# Master_V4_1.net
KiCad netlist of a schematic drawn in Altium Designer
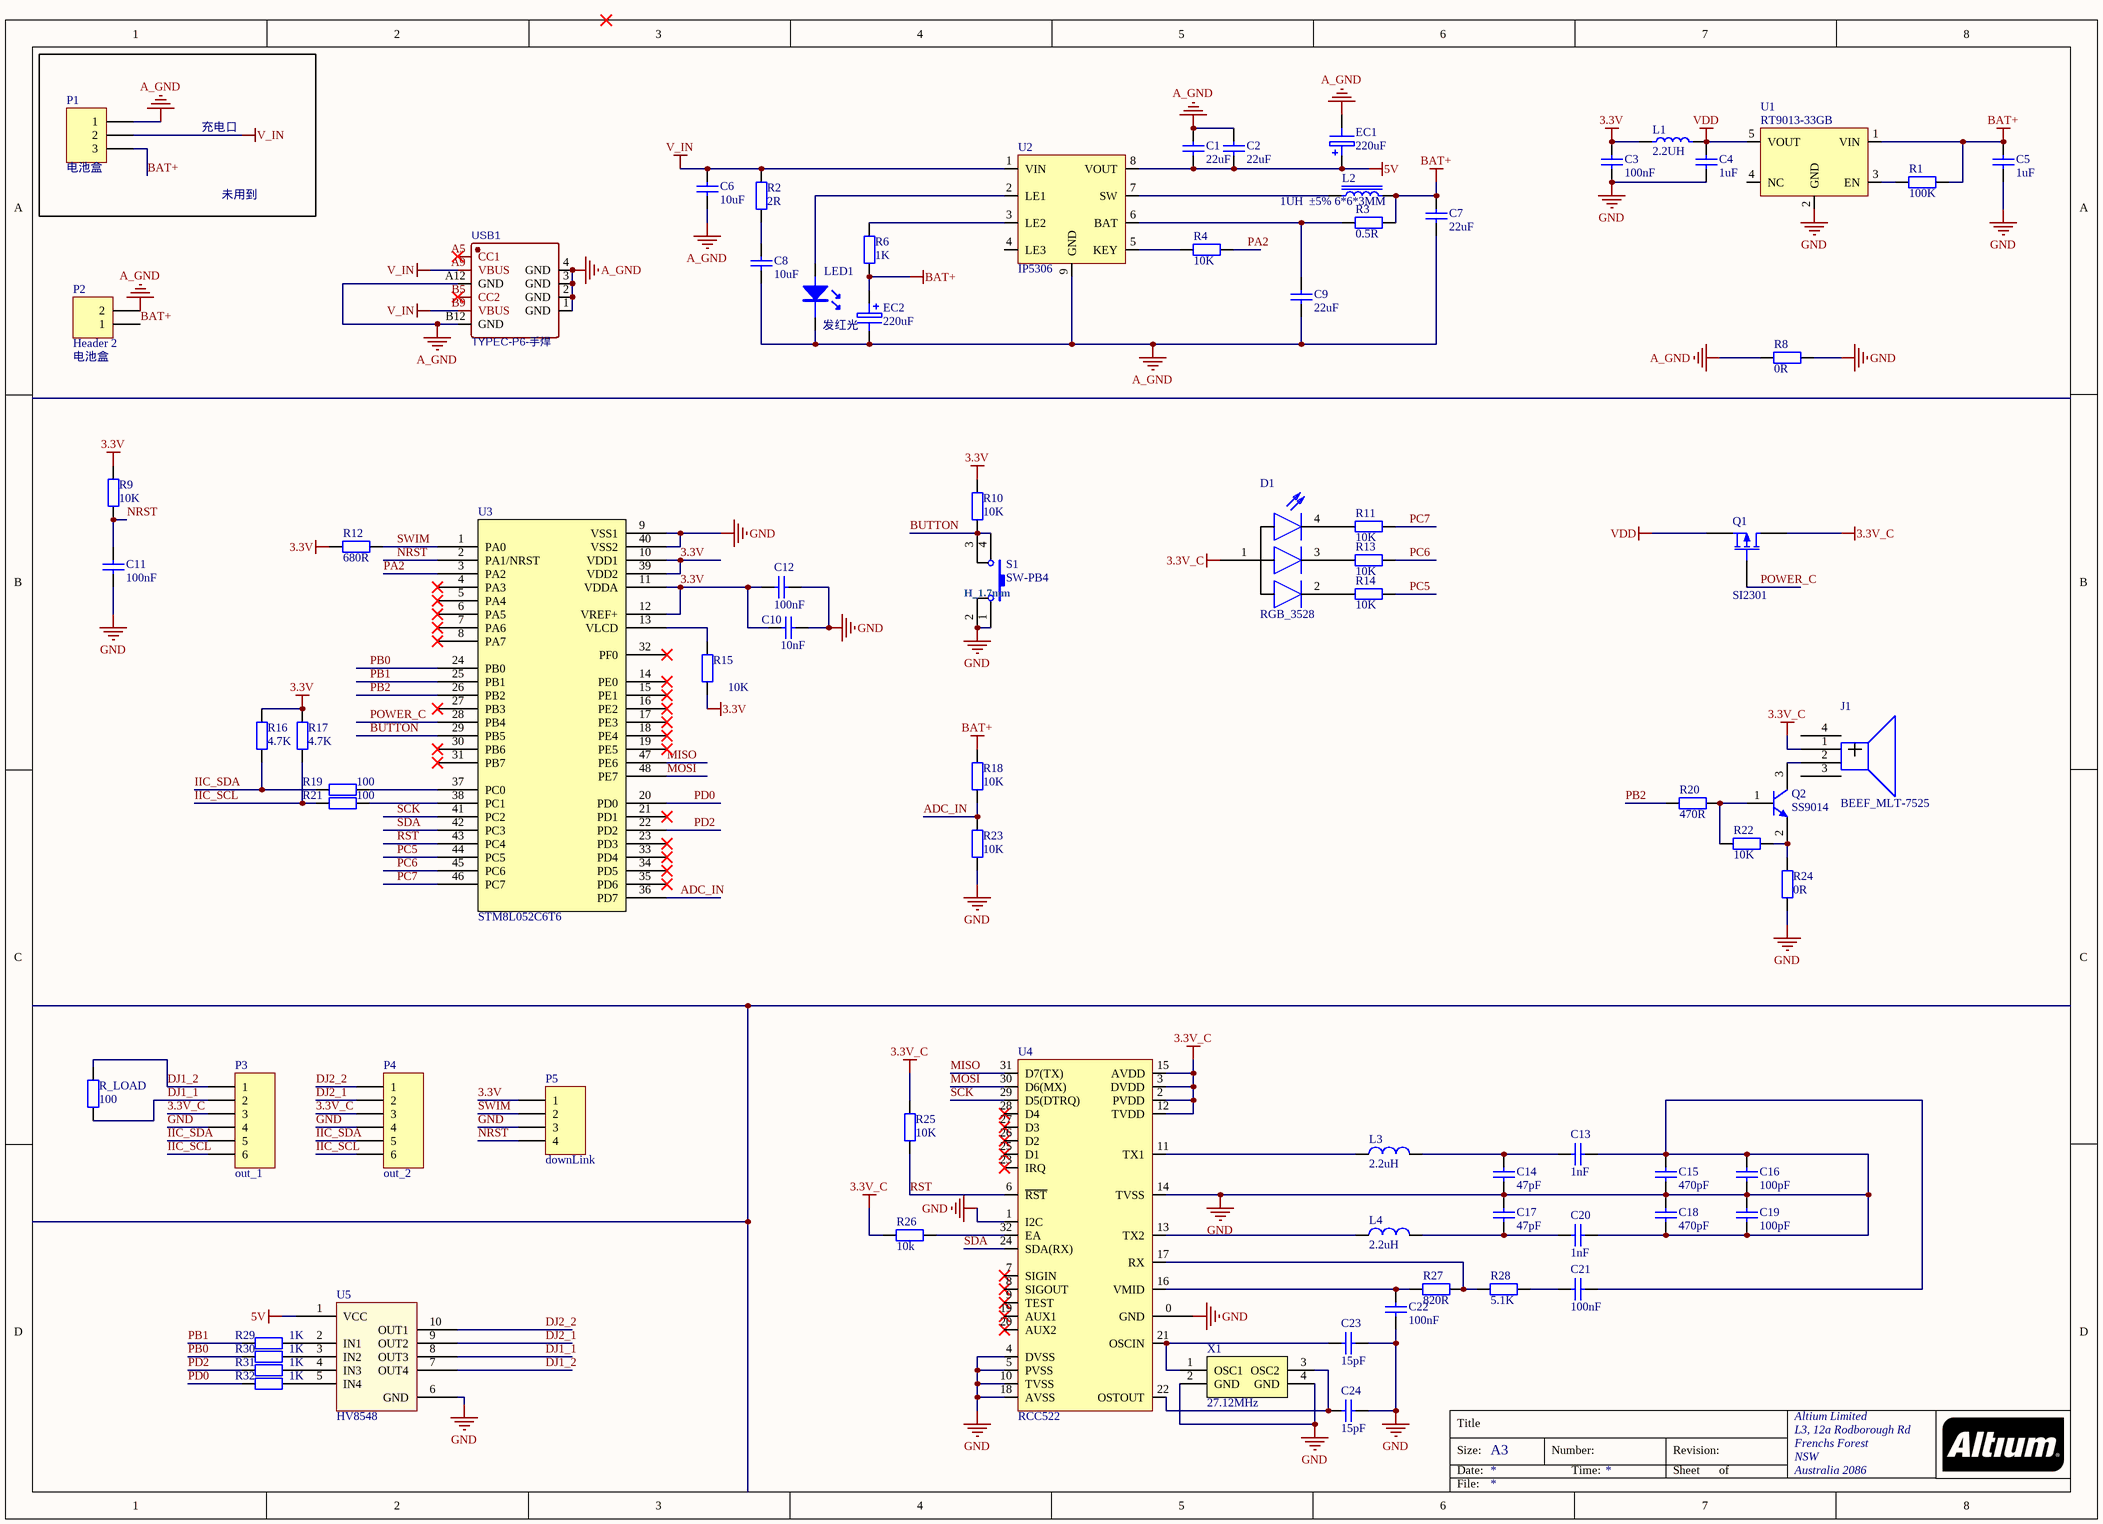
[diagram p0: Master_V4.1.SchDoc]

(export (version "E")
  (design (tool "Eeschema 10.0.6"))
  (components
    (comp (ref "C1")
      (value "22uF")
      (footprint "C-0603")
      (description "贴片瓷片电容")
      (fields (field (name "PUBLISHER") "Altium Limited"))
      (libsource (lib "PCB_Project") (part "22uF"))
    )
    (comp (ref "C2")
      (value "22uF")
      (footprint "C-0603")
      (description "贴片瓷片电容")
      (fields (field (name "PUBLISHER") "Altium Limited"))
      (libsource (lib "PCB_Project") (part "22uF"))
    )
    (comp (ref "C3")
      (value "100nF")
      (footprint "C-0603")
      (description "贴片瓷片电容")
      (fields (field (name "PUBLISHER") "Altium Limited"))
      (libsource (lib "PCB_Project") (part "100nF"))
    )
    (comp (ref "C4")
      (value "1uF")
      (footprint "C-0603")
      (description "贴片瓷片电容")
      (fields (field (name "PUBLISHER") "Altium Limited"))
      (libsource (lib "PCB_Project") (part "1uF"))
    )
    (comp (ref "C5")
      (value "1uF")
      (footprint "C-0603")
      (description "贴片瓷片电容")
      (fields (field (name "PUBLISHER") "Altium Limited"))
      (libsource (lib "PCB_Project") (part "1uF"))
    )
    (comp (ref "C6")
      (value "10uF")
      (footprint "C-0603")
      (description "贴片瓷片电容")
      (fields (field (name "PUBLISHER") "Altium Limited"))
      (libsource (lib "PCB_Project") (part "10uF"))
    )
    (comp (ref "C7")
      (value "22uF")
      (footprint "C-0603")
      (description "贴片瓷片电容")
      (fields (field (name "PUBLISHER") "Altium Limited"))
      (libsource (lib "PCB_Project") (part "22uF"))
    )
    (comp (ref "C8")
      (value "10uF")
      (footprint "C-0603")
      (description "贴片瓷片电容")
      (fields (field (name "PUBLISHER") "Altium Limited"))
      (libsource (lib "PCB_Project") (part "10uF"))
    )
    (comp (ref "C9")
      (value "22uF")
      (footprint "C-0603")
      (description "贴片瓷片电容")
      (fields (field (name "PUBLISHER") "Altium Limited"))
      (libsource (lib "PCB_Project") (part "22uF"))
    )
    (comp (ref "C10")
      (value "10nF")
      (footprint "C-0603")
      (description "贴片瓷片电容")
      (fields (field (name "PUBLISHER") "Altium Limited"))
      (libsource (lib "PCB_Project") (part "10nF"))
    )
    (comp (ref "C11")
      (value "100nF")
      (footprint "C-0603")
      (description "贴片瓷片电容")
      (fields (field (name "PUBLISHER") "Altium Limited"))
      (libsource (lib "PCB_Project") (part "100nF"))
    )
    (comp (ref "C12")
      (value "100nF")
      (footprint "C-0603")
      (description "贴片瓷片电容")
      (fields (field (name "PUBLISHER") "Altium Limited"))
      (libsource (lib "PCB_Project") (part "100nF"))
    )
    (comp (ref "C13")
      (value "1nF")
      (footprint "C-0603")
      (description "贴片瓷片电容")
      (fields (field (name "PUBLISHER") "Altium Limited"))
      (libsource (lib "PCB_Project") (part "1nF"))
    )
    (comp (ref "C14")
      (value "47pF")
      (footprint "C-0603")
      (description "贴片瓷片电容")
      (fields (field (name "PUBLISHER") "Altium Limited"))
      (libsource (lib "PCB_Project") (part "47pF"))
    )
    (comp (ref "C15")
      (value "470pF")
      (footprint "C-0603")
      (description "贴片瓷片电容")
      (fields (field (name "PUBLISHER") "Altium Limited"))
      (libsource (lib "PCB_Project") (part "470pF"))
    )
    (comp (ref "C16")
      (value "100pF")
      (footprint "C-0603")
      (description "贴片瓷片电容")
      (fields (field (name "PUBLISHER") "Altium Limited"))
      (libsource (lib "PCB_Project") (part "100pF"))
    )
    (comp (ref "C17")
      (value "47pF")
      (footprint "C-0603")
      (description "贴片瓷片电容")
      (fields (field (name "PUBLISHER") "Altium Limited"))
      (libsource (lib "PCB_Project") (part "47pF"))
    )
    (comp (ref "C18")
      (value "470pF")
      (footprint "C-0603")
      (description "贴片瓷片电容")
      (fields (field (name "PUBLISHER") "Altium Limited"))
      (libsource (lib "PCB_Project") (part "470pF"))
    )
    (comp (ref "C19")
      (value "100pF")
      (footprint "C-0603")
      (description "贴片瓷片电容")
      (fields (field (name "PUBLISHER") "Altium Limited"))
      (libsource (lib "PCB_Project") (part "100pF"))
    )
    (comp (ref "C20")
      (value "1nF")
      (footprint "C-0603")
      (description "贴片瓷片电容")
      (fields (field (name "PUBLISHER") "Altium Limited"))
      (libsource (lib "PCB_Project") (part "1nF"))
    )
    (comp (ref "C21")
      (value "100nF")
      (footprint "C-0603")
      (description "贴片瓷片电容")
      (fields (field (name "PUBLISHER") "Altium Limited"))
      (libsource (lib "PCB_Project") (part "100nF"))
    )
    (comp (ref "C22")
      (value "100nF")
      (footprint "C-0603")
      (description "贴片瓷片电容")
      (fields (field (name "PUBLISHER") "Altium Limited"))
      (libsource (lib "PCB_Project") (part "100nF"))
    )
    (comp (ref "C23")
      (value "15pF")
      (footprint "C-0603")
      (description "贴片瓷片电容")
      (fields (field (name "PUBLISHER") "Altium Limited"))
      (libsource (lib "PCB_Project") (part "15pF"))
    )
    (comp (ref "C24")
      (value "15pF")
      (footprint "C-0603")
      (description "贴片瓷片电容")
      (fields (field (name "PUBLISHER") "Altium Limited"))
      (libsource (lib "PCB_Project") (part "15pF"))
    )
    (comp (ref "D1")
      (value "RGB_3528")
      (footprint "SMD3528")
      (libsource (lib "PCB_Project") (part "RGB_3528"))
    )
    (comp (ref "EC1")
      (value "220uF")
      (footprint "CAP-3528")
      (description "3528钽电容")
      (libsource (lib "PCB_Project") (part "220uF"))
    )
    (comp (ref "EC2")
      (value "220uF")
      (footprint "CAP-3528")
      (description "3528钽电容")
      (libsource (lib "PCB_Project") (part "220uF"))
    )
    (comp (ref "J1")
      (value "BEEF_MLT-7525")
      (footprint "MLT-7525")
      (libsource (lib "SwipeMaster") (part "BEEF_MLT-7525"))
    )
    (comp (ref "L1") (value "2.2UH") (footprint "0805") (libsource (lib "*") (part "INCT")))
    (comp (ref "L2") (value "1UH  ±5% 6*6*3MM") (footprint "L") (libsource (lib "*") (part "INCT_1")))
    (comp (ref "L3") (value "2.2uH") (footprint "0805") (libsource (lib "Schlib1") (part "INDUCTANCE")))
    (comp (ref "L4") (value "2.2uH") (footprint "0805") (libsource (lib "Schlib1") (part "INDUCTANCE")))
    (comp (ref "LED1") (value "发红光") (footprint "LED0603_RED") (libsource (lib "*") (part "LED")))
    (comp (ref "P1")
      (value "电池盒")
      (footprint "POWER_3_改")
      (description "Header, 3-Pin")
      (fields (field (name "PUBLISHER") "Altium Limited"))
      (libsource (lib "Miscellaneous Connectors") (part "Header 3"))
    )
    (comp (ref "P2")
      (value "Header 2")
      (footprint "HDR1X2")
      (description "Header, 2-Pin")
      (fields (field (name "PUBLISHER") "Altium Limited"))
      (libsource (lib "Miscellaneous Connectors") (part "Header 2"))
    )
    (comp (ref "P3")
      (value "out_1")
      (footprint "乐高水晶头")
      (description "Header, 6-Pin")
      (fields (field (name "PUBLISHER") "Altium Limited"))
      (libsource (lib "Miscellaneous Connectors") (part "Header 6"))
    )
    (comp (ref "P4")
      (value "out_2")
      (footprint "乐高水晶头")
      (description "Header, 6-Pin")
      (fields (field (name "PUBLISHER") "Altium Limited"))
      (libsource (lib "Miscellaneous Connectors") (part "Header 6"))
    )
    (comp (ref "P5")
      (value "downLink")
      (footprint "DOWNLOAD_dan")
      (description "Header, 4-Pin")
      (fields (field (name "PUBLISHER") "Altium Limited"))
      (libsource (lib "Miscellaneous Connectors") (part "Header 4"))
    )
    (comp (ref "Q1")
      (value "SI2301")
      (footprint "SOT-23(SOT-23-3)")
      (description "P-Channel MOSFET")
      (fields (field (name "PUBLISHER") "Altium Limited"))
      (libsource (lib "Miscellaneous Devices") (part "MOSFET-P"))
    )
    (comp (ref "Q2")
      (value "SS9014")
      (footprint "SOT23-3")
      (description "NPN贴片三极管")
      (fields (field (name "PUBLISHER") "Altium Limited"))
      (libsource (lib "fszhang_P") (part "SS9014"))
    )
    (comp (ref "R1")
      (value "100K")
      (footprint "0603-1")
      (description "贴片电阻")
      (fields (field (name "PUBLISHER") "Altium Limited"))
      (libsource (lib "PCB_Project") (part "100K"))
    )
    (comp (ref "R2")
      (value "2R")
      (footprint "0603-1")
      (description "贴片电阻")
      (fields (field (name "PUBLISHER") "Altium Limited"))
      (libsource (lib "PCB_Project") (part "2R"))
    )
    (comp (ref "R3")
      (value "0.5R")
      (footprint "0603-1")
      (description "贴片电阻")
      (fields (field (name "PUBLISHER") "Altium Limited"))
      (libsource (lib "PCB_Project") (part "0.5R"))
    )
    (comp (ref "R4")
      (value "10K")
      (footprint "0603-1")
      (description "贴片电阻")
      (fields (field (name "PUBLISHER") "Altium Limited"))
      (libsource (lib "") (part "10K_1"))
    )
    (comp (ref "R6")
      (value "1K")
      (footprint "0603-1")
      (description "贴片电阻")
      (fields (field (name "PUBLISHER") "Altium Limited"))
      (libsource (lib "PCB_Project") (part "1K"))
    )
    (comp (ref "R8")
      (value "0R")
      (footprint "0603-1")
      (description "贴片电阻")
      (fields (field (name "PUBLISHER") "Altium Limited"))
      (libsource (lib "") (part "0R_1"))
    )
    (comp (ref "R9")
      (value "10K")
      (footprint "0603-1")
      (description "贴片电阻")
      (fields (field (name "PUBLISHER") "Altium Limited"))
      (libsource (lib "PCB_Project") (part "10K"))
    )
    (comp (ref "R10")
      (value "10K")
      (footprint "0603-1")
      (description "贴片电阻")
      (fields (field (name "PUBLISHER") "Altium Limited"))
      (libsource (lib "") (part "10K_1"))
    )
    (comp (ref "R11")
      (value "10K")
      (footprint "0603-1")
      (description "贴片电阻")
      (fields (field (name "PUBLISHER") "Altium Limited"))
      (libsource (lib "PCB_Project") (part "10K"))
    )
    (comp (ref "R12")
      (value "680R")
      (footprint "0603-1")
      (description "贴片电阻")
      (fields (field (name "PUBLISHER") "Altium Limited"))
      (libsource (lib "PCB_Project") (part "680R"))
    )
    (comp (ref "R13")
      (value "10K")
      (footprint "0603-1")
      (description "贴片电阻")
      (fields (field (name "PUBLISHER") "Altium Limited"))
      (libsource (lib "PCB_Project") (part "10K"))
    )
    (comp (ref "R14")
      (value "10K")
      (footprint "0603-1")
      (description "贴片电阻")
      (fields (field (name "PUBLISHER") "Altium Limited"))
      (libsource (lib "PCB_Project") (part "10K"))
    )
    (comp (ref "R15")
      (value "10K")
      (footprint "0603-1")
      (description "贴片电阻")
      (fields (field (name "PUBLISHER") "Altium Limited"))
      (libsource (lib "PCB_Project") (part "10K"))
    )
    (comp (ref "R16")
      (value "4.7K")
      (footprint "0603-1")
      (description "贴片电阻")
      (fields (field (name "PUBLISHER") "Altium Limited"))
      (libsource (lib "PCB_Project") (part "4.7K"))
    )
    (comp (ref "R17")
      (value "4.7K")
      (footprint "0603-1")
      (description "贴片电阻")
      (fields (field (name "PUBLISHER") "Altium Limited"))
      (libsource (lib "PCB_Project") (part "4.7K"))
    )
    (comp (ref "R18")
      (value "10K")
      (footprint "0603-1")
      (description "贴片电阻")
      (fields (field (name "PUBLISHER") "Altium Limited"))
      (libsource (lib "") (part "10K_2"))
    )
    (comp (ref "R19")
      (value "100")
      (footprint "0603-1")
      (description "贴片电阻")
      (fields (field (name "Comment") "Res1") (field (name "PUBLISHER") "Altium Limited"))
      (libsource (lib "fszhang_P") (part "Res1"))
    )
    (comp (ref "R20")
      (value "470R")
      (footprint "0603-1")
      (description "贴片电阻")
      (fields (field (name "PUBLISHER") "Altium Limited"))
      (libsource (lib "PCB_Project") (part "470R"))
    )
    (comp (ref "R21")
      (value "100")
      (footprint "0603-1")
      (description "贴片电阻")
      (fields (field (name "Comment") "Res1") (field (name "PUBLISHER") "Altium Limited"))
      (libsource (lib "fszhang_P") (part "Res1"))
    )
    (comp (ref "R22")
      (value "10K")
      (footprint "0603-1")
      (description "贴片电阻")
      (fields (field (name "PUBLISHER") "Altium Limited"))
      (libsource (lib "") (part "10K_1"))
    )
    (comp (ref "R23")
      (value "10K")
      (footprint "0603-1")
      (description "贴片电阻")
      (fields (field (name "PUBLISHER") "Altium Limited"))
      (libsource (lib "") (part "10K_2"))
    )
    (comp (ref "R24")
      (value "0R")
      (footprint "0603-1")
      (description "贴片电阻")
      (fields (field (name "PUBLISHER") "Altium Limited"))
      (libsource (lib "PCB_Project") (part "0R"))
    )
    (comp (ref "R25")
      (value "10K")
      (footprint "0603-1")
      (description "贴片电阻")
      (fields (field (name "PUBLISHER") "Altium Limited"))
      (libsource (lib "PCB_Project") (part "10K"))
    )
    (comp (ref "R26")
      (value "10k")
      (footprint "0603-1")
      (description "贴片电阻")
      (fields (field (name "PUBLISHER") "Altium Limited"))
      (libsource (lib "") (part "1K_1"))
    )
    (comp (ref "R27")
      (value "820R")
      (footprint "0603-1")
      (description "贴片电阻")
      (fields (field (name "PUBLISHER") "Altium Limited"))
      (libsource (lib "PCB_Project") (part "820R"))
    )
    (comp (ref "R28")
      (value "5.1K")
      (footprint "0603-1")
      (description "贴片电阻")
      (fields (field (name "PUBLISHER") "Altium Limited"))
      (libsource (lib "PCB_Project") (part "5.1K"))
    )
    (comp (ref "R29")
      (value "1K")
      (footprint "0603-1")
      (description "贴片电阻")
      (fields (field (name "PUBLISHER") "Altium Limited"))
      (libsource (lib "") (part "1K_1"))
    )
    (comp (ref "R30")
      (value "1K")
      (footprint "0603-1")
      (description "贴片电阻")
      (fields (field (name "PUBLISHER") "Altium Limited"))
      (libsource (lib "") (part "1K_1"))
    )
    (comp (ref "R31")
      (value "1K")
      (footprint "0603-1")
      (description "贴片电阻")
      (fields (field (name "PUBLISHER") "Altium Limited"))
      (libsource (lib "") (part "1K_1"))
    )
    (comp (ref "R32")
      (value "1K")
      (footprint "0603-1")
      (description "贴片电阻")
      (fields (field (name "PUBLISHER") "Altium Limited"))
      (libsource (lib "") (part "1K_1"))
    )
    (comp (ref "R_LOAD")
      (value "100")
      (footprint "0603-1")
      (description "贴片电阻")
      (fields (field (name "Comment") "Res1") (field (name "PUBLISHER") "Altium Limited"))
      (libsource (lib "") (part "Res1_1"))
    )
    (comp (ref "S1")
      (value "SW-PB4")
      (footprint "SMD_5*5mm")
      (description "微动开关")
      (fields (field (name "PUBLISHER") "Altium Limited"))
      (libsource (lib "fszhang_P") (part "SW-PB4"))
    )
    (comp (ref "U1") (value "RT9013-33GB") (footprint "SOT-23-5") (libsource (lib "*") (part "RT9013-33GB")))
    (comp (ref "U2") (value "IP5306") (footprint "SOP-8") (libsource (lib "*") (part "IP5306")))
    (comp (ref "U3")
      (value "STM8L052C6T6")
      (footprint "LQFP-48")
      (libsource (lib "SwipeMaster") (part "STM8L052C6T6"))
    )
    (comp (ref "U4")
      (value "RCC522")
      (footprint "QFN-32_5*5")
      (libsource (lib "SwipeMaster") (part "RCC522"))
    )
    (comp (ref "U5") (value "HV8548") (footprint "SOP10") (libsource (lib "XJL公司网口") (part "LV8548")))
    (comp (ref "USB1")
      (value "TYPEC-P6-手焊")
      (footprint "TYPE_C_6P")
      (fields
        (field (name "BOM_SUPPLIER PART") "C720626")
        (field (name "BOM_MANUFACTURER PART") "TYPEC-250D-BCP6")
        (field (name "CONTRIBUTOR") "LCSC")
      )
      (libsource (lib "Sheet_1_2021-06-05") (part "TYPEC-P6-手焊"))
    )
    (comp (ref "X1")
      (value "27.12MHz")
      (footprint "SMD_3225")
      (libsource (lib "SwipeMaster") (part "27.12MHz"))
    )
  )
  (nets
    (net (code "1") (name "/ADC_IN") (class "Default")
      (node (ref "R18") (pin "2") (pinfunction "2_2") (pintype "passive"))
      (node (ref "R23") (pin "1") (pinfunction "1_1") (pintype "passive"))
      (node (ref "U3") (pin "36") (pinfunction "PD7_36") (pintype "passive"))
    )
    (net (code "2") (name "/BUTTON") (class "Default")
      (node (ref "R10") (pin "1") (pinfunction "1_1") (pintype "passive"))
      (node (ref "S1") (pin "3") (pinfunction "3_3") (pintype "passive"))
      (node (ref "S1") (pin "4") (pinfunction "4_4") (pintype "passive"))
      (node (ref "U3") (pin "29") (pinfunction "PB5_29") (pintype "passive"))
    )
    (net (code "3") (name "/DJ1_1") (class "Default")
      (node (ref "P3") (pin "2") (pinfunction "2_2") (pintype "passive"))
      (node (ref "R_LOAD") (pin "2") (pinfunction "2_2") (pintype "passive"))
      (node (ref "U5") (pin "8") (pinfunction "OUT3_8") (pintype "passive"))
    )
    (net (code "4") (name "/DJ1_2") (class "Default")
      (node (ref "P3") (pin "1") (pinfunction "1_1") (pintype "passive"))
      (node (ref "R_LOAD") (pin "1") (pinfunction "1_1") (pintype "passive"))
      (node (ref "U5") (pin "7") (pinfunction "OUT4_7") (pintype "passive"))
    )
    (net (code "5") (name "/DJ2_1") (class "Default")
      (node (ref "P4") (pin "2") (pinfunction "2_2") (pintype "passive"))
      (node (ref "U5") (pin "9") (pinfunction "OUT2_9") (pintype "passive"))
    )
    (net (code "6") (name "/DJ2_2") (class "Default")
      (node (ref "P4") (pin "1") (pinfunction "1_1") (pintype "passive"))
      (node (ref "U5") (pin "10") (pinfunction "OUT1_10") (pintype "passive"))
    )
    (net (code "7") (name "/IIC_SCL") (class "Default")
      (node (ref "P3") (pin "6") (pinfunction "6_6") (pintype "passive"))
      (node (ref "P4") (pin "6") (pinfunction "6_6") (pintype "passive"))
      (node (ref "R17") (pin "1") (pinfunction "1_1") (pintype "passive"))
      (node (ref "R21") (pin "2") (pinfunction "2_2") (pintype "passive"))
    )
    (net (code "8") (name "/IIC_SDA") (class "Default")
      (node (ref "P3") (pin "5") (pinfunction "5_5") (pintype "passive"))
      (node (ref "P4") (pin "5") (pinfunction "5_5") (pintype "passive"))
      (node (ref "R16") (pin "1") (pinfunction "1_1") (pintype "passive"))
      (node (ref "R19") (pin "2") (pinfunction "2_2") (pintype "passive"))
    )
    (net (code "9") (name "/MISO") (class "Default")
      (node (ref "U3") (pin "47") (pinfunction "PE6_47") (pintype "passive"))
      (node (ref "U4") (pin "31") (pinfunction "D7(TX)_31") (pintype "passive"))
    )
    (net (code "10") (name "/MOSI") (class "Default")
      (node (ref "U3") (pin "48") (pinfunction "PE7_48") (pintype "passive"))
      (node (ref "U4") (pin "30") (pinfunction "D6(MX)_30") (pintype "passive"))
    )
    (net (code "11") (name "/NRST") (class "Default")
      (node (ref "C11") (pin "1") (pinfunction "1_1") (pintype "passive"))
      (node (ref "P5") (pin "4") (pinfunction "4_4") (pintype "passive"))
      (node (ref "R9") (pin "1") (pinfunction "1_1") (pintype "passive"))
      (node (ref "U3") (pin "2") (pinfunction "PA1/NRST_2") (pintype "passive"))
    )
    (net (code "12") (name "/PA2") (class "Default")
      (node (ref "R4") (pin "2") (pinfunction "2_2") (pintype "passive"))
      (node (ref "U3") (pin "3") (pinfunction "PA2_3") (pintype "passive"))
    )
    (net (code "13") (name "/PB0") (class "Default")
      (node (ref "R30") (pin "1") (pinfunction "1_1") (pintype "passive"))
      (node (ref "U3") (pin "24") (pinfunction "PB0_24") (pintype "passive"))
    )
    (net (code "14") (name "/PB1") (class "Default")
      (node (ref "R29") (pin "1") (pinfunction "1_1") (pintype "passive"))
      (node (ref "U3") (pin "25") (pinfunction "PB1_25") (pintype "passive"))
    )
    (net (code "15") (name "/PB2") (class "Default")
      (node (ref "R20") (pin "1") (pinfunction "1_1") (pintype "passive"))
      (node (ref "U3") (pin "26") (pinfunction "PB2_26") (pintype "passive"))
    )
    (net (code "16") (name "/PC5") (class "Default")
      (node (ref "R14") (pin "2") (pinfunction "2_2") (pintype "passive"))
      (node (ref "U3") (pin "44") (pinfunction "PC5_44") (pintype "passive"))
    )
    (net (code "17") (name "/PC6") (class "Default")
      (node (ref "R13") (pin "2") (pinfunction "2_2") (pintype "passive"))
      (node (ref "U3") (pin "45") (pinfunction "PC6_45") (pintype "passive"))
    )
    (net (code "18") (name "/PC7") (class "Default")
      (node (ref "R11") (pin "2") (pinfunction "2_2") (pintype "passive"))
      (node (ref "U3") (pin "46") (pinfunction "PC7_46") (pintype "passive"))
    )
    (net (code "19") (name "/PD0") (class "Default")
      (node (ref "R32") (pin "1") (pinfunction "1_1") (pintype "passive"))
      (node (ref "U3") (pin "20") (pinfunction "PD0_20") (pintype "passive"))
    )
    (net (code "20") (name "/PD2") (class "Default")
      (node (ref "R31") (pin "1") (pinfunction "1_1") (pintype "passive"))
      (node (ref "U3") (pin "22") (pinfunction "PD2_22") (pintype "passive"))
    )
    (net (code "21") (name "/POWER_C") (class "Default")
      (node (ref "Q1") (pin "1") (pinfunction "G_1") (pintype "passive"))
      (node (ref "U3") (pin "28") (pinfunction "PB4_28") (pintype "passive"))
    )
    (net (code "22") (name "/RST") (class "Default")
      (node (ref "R25") (pin "1") (pinfunction "1_1") (pintype "passive"))
      (node (ref "U3") (pin "43") (pinfunction "PC4_43") (pintype "passive"))
      (node (ref "U4") (pin "6") (pinfunction "~{RST}_6") (pintype "passive"))
    )
    (net (code "23") (name "/SCK") (class "Default")
      (node (ref "U3") (pin "41") (pinfunction "PC2_41") (pintype "passive"))
      (node (ref "U4") (pin "29") (pinfunction "D5(DTRQ)_29") (pintype "passive"))
    )
    (net (code "24") (name "/SDA") (class "Default")
      (node (ref "U3") (pin "42") (pinfunction "PC3_42") (pintype "passive"))
      (node (ref "U4") (pin "24") (pinfunction "SDA(RX)_24") (pintype "passive"))
    )
    (net (code "25") (name "/SWIM") (class "Default")
      (node (ref "P5") (pin "2") (pinfunction "2_2") (pintype "passive"))
      (node (ref "R12") (pin "2") (pinfunction "2_2") (pintype "passive"))
      (node (ref "U3") (pin "1") (pinfunction "PA0_1") (pintype "passive"))
    )
    (net (code "26") (name "3.3V") (class "Default")
      (node (ref "C10") (pin "2") (pinfunction "2_2") (pintype "passive"))
      (node (ref "C12") (pin "2") (pinfunction "2_2") (pintype "passive"))
      (node (ref "C3") (pin "1") (pinfunction "1_1") (pintype "passive"))
      (node (ref "L1") (pin "1") (pinfunction "1_1") (pintype "passive"))
      (node (ref "P5") (pin "1") (pinfunction "1_1") (pintype "passive"))
      (node (ref "R10") (pin "2") (pinfunction "2_2") (pintype "passive"))
      (node (ref "R12") (pin "1") (pinfunction "1_1") (pintype "passive"))
      (node (ref "R15") (pin "1") (pinfunction "1_1") (pintype "passive"))
      (node (ref "R16") (pin "2") (pinfunction "2_2") (pintype "passive"))
      (node (ref "R17") (pin "2") (pinfunction "2_2") (pintype "passive"))
      (node (ref "R9") (pin "2") (pinfunction "2_2") (pintype "passive"))
      (node (ref "U3") (pin "10") (pinfunction "VDD1_10") (pintype "passive"))
      (node (ref "U3") (pin "11") (pinfunction "VDDA_11") (pintype "passive"))
      (node (ref "U3") (pin "12") (pinfunction "VREF+_12") (pintype "passive"))
      (node (ref "U3") (pin "39") (pinfunction "VDD2_39") (pintype "passive"))
    )
    (net (code "27") (name "3.3V_C") (class "Default")
      (node (ref "D1") (pin "1") (pinfunction "1_1") (pintype "passive"))
      (node (ref "J1") (pin "1") (pinfunction "1_1") (pintype "passive"))
      (node (ref "P3") (pin "3") (pinfunction "3_3") (pintype "passive"))
      (node (ref "P4") (pin "3") (pinfunction "3_3") (pintype "passive"))
      (node (ref "Q1") (pin "3") (pinfunction "D_3") (pintype "passive"))
      (node (ref "R25") (pin "2") (pinfunction "2_2") (pintype "passive"))
      (node (ref "R26") (pin "1") (pinfunction "1_1") (pintype "passive"))
      (node (ref "U4") (pin "12") (pinfunction "TVDD_12") (pintype "passive"))
      (node (ref "U4") (pin "15") (pinfunction "AVDD_15") (pintype "passive"))
      (node (ref "U4") (pin "2") (pinfunction "PVDD_2") (pintype "passive"))
      (node (ref "U4") (pin "3") (pinfunction "DVDD_3") (pintype "passive"))
    )
    (net (code "28") (name "5V") (class "Default")
      (node (ref "C1") (pin "2") (pinfunction "2_2") (pintype "passive"))
      (node (ref "C2") (pin "2") (pinfunction "2_2") (pintype "passive"))
      (node (ref "EC1") (pin "1") (pinfunction "1_1") (pintype "passive"))
      (node (ref "U2") (pin "8") (pinfunction "VOUT_8") (pintype "passive"))
      (node (ref "U5") (pin "1") (pinfunction "VCC_1") (pintype "passive"))
    )
    (net (code "29") (name "A_GND") (class "Default")
      (node (ref "C1") (pin "1") (pinfunction "1_1") (pintype "passive"))
      (node (ref "C2") (pin "1") (pinfunction "1_1") (pintype "passive"))
      (node (ref "C6") (pin "2") (pinfunction "2_2") (pintype "passive"))
      (node (ref "C7") (pin "2") (pinfunction "2_2") (pintype "passive"))
      (node (ref "C8") (pin "1") (pinfunction "1_1") (pintype "passive"))
      (node (ref "C9") (pin "2") (pinfunction "2_2") (pintype "passive"))
      (node (ref "EC1") (pin "2") (pinfunction "2_2") (pintype "passive"))
      (node (ref "EC2") (pin "2") (pinfunction "2_2") (pintype "passive"))
      (node (ref "LED1") (pin "2") (pinfunction "2_2") (pintype "passive"))
      (node (ref "P1") (pin "1") (pinfunction "1_1") (pintype "passive"))
      (node (ref "P2") (pin "2") (pinfunction "2_2") (pintype "passive"))
      (node (ref "R8") (pin "1") (pinfunction "1_1") (pintype "passive"))
      (node (ref "U2") (pin "9") (pinfunction "GND_9") (pintype "passive"))
      (node (ref "USB1") (pin "1") (pinfunction "GND_1") (pintype "passive"))
      (node (ref "USB1") (pin "2") (pinfunction "GND_2") (pintype "passive"))
      (node (ref "USB1") (pin "3") (pinfunction "GND_3") (pintype "passive"))
      (node (ref "USB1") (pin "4") (pinfunction "GND_4") (pintype "passive"))
      (node (ref "USB1") (pin "A12") (pinfunction "GND_A12") (pintype "passive"))
      (node (ref "USB1") (pin "B12") (pinfunction "GND_B12") (pintype "passive"))
    )
    (net (code "30") (name "BAT+") (class "Default")
      (node (ref "C5") (pin "2") (pinfunction "2_2") (pintype "passive"))
      (node (ref "C7") (pin "1") (pinfunction "1_1") (pintype "passive"))
      (node (ref "EC2") (pin "1") (pinfunction "1_1") (pintype "passive"))
      (node (ref "L2") (pin "2") (pinfunction "2_2") (pintype "passive"))
      (node (ref "P1") (pin "3") (pinfunction "3_3") (pintype "passive"))
      (node (ref "P2") (pin "1") (pinfunction "1_1") (pintype "passive"))
      (node (ref "R1") (pin "2") (pinfunction "2_2") (pintype "passive"))
      (node (ref "R18") (pin "1") (pinfunction "1_1") (pintype "passive"))
      (node (ref "R3") (pin "2") (pinfunction "2_2") (pintype "passive"))
      (node (ref "R6") (pin "1") (pinfunction "1_1") (pintype "passive"))
      (node (ref "U1") (pin "1") (pinfunction "VIN_1") (pintype "passive"))
    )
    (net (code "31") (name "GND") (class "Default")
      (node (ref "C10") (pin "1") (pinfunction "1_1") (pintype "passive"))
      (node (ref "C11") (pin "2") (pinfunction "2_2") (pintype "passive"))
      (node (ref "C12") (pin "1") (pinfunction "1_1") (pintype "passive"))
      (node (ref "C13") (pin "2") (pinfunction "2_2") (pintype "passive"))
      (node (ref "C14") (pin "1") (pinfunction "1_1") (pintype "passive"))
      (node (ref "C15") (pin "1") (pinfunction "1_1") (pintype "passive"))
      (node (ref "C15") (pin "2") (pinfunction "2_2") (pintype "passive"))
      (node (ref "C16") (pin "1") (pinfunction "1_1") (pintype "passive"))
      (node (ref "C16") (pin "2") (pinfunction "2_2") (pintype "passive"))
      (node (ref "C17") (pin "2") (pinfunction "2_2") (pintype "passive"))
      (node (ref "C18") (pin "1") (pinfunction "1_1") (pintype "passive"))
      (node (ref "C18") (pin "2") (pinfunction "2_2") (pintype "passive"))
      (node (ref "C19") (pin "1") (pinfunction "1_1") (pintype "passive"))
      (node (ref "C19") (pin "2") (pinfunction "2_2") (pintype "passive"))
      (node (ref "C20") (pin "2") (pinfunction "2_2") (pintype "passive"))
      (node (ref "C21") (pin "1") (pinfunction "1_1") (pintype "passive"))
      (node (ref "C22") (pin "1") (pinfunction "1_1") (pintype "passive"))
      (node (ref "C23") (pin "2") (pinfunction "2_2") (pintype "passive"))
      (node (ref "C24") (pin "2") (pinfunction "2_2") (pintype "passive"))
      (node (ref "C3") (pin "2") (pinfunction "2_2") (pintype "passive"))
      (node (ref "C4") (pin "1") (pinfunction "1_1") (pintype "passive"))
      (node (ref "C5") (pin "1") (pinfunction "1_1") (pintype "passive"))
      (node (ref "P3") (pin "4") (pinfunction "4_4") (pintype "passive"))
      (node (ref "P4") (pin "4") (pinfunction "4_4") (pintype "passive"))
      (node (ref "P5") (pin "3") (pinfunction "3_3") (pintype "passive"))
      (node (ref "R23") (pin "2") (pinfunction "2_2") (pintype "passive"))
      (node (ref "R24") (pin "1") (pinfunction "1_1") (pintype "passive"))
      (node (ref "R8") (pin "2") (pinfunction "2_2") (pintype "passive"))
      (node (ref "S1") (pin "1") (pinfunction "1_1") (pintype "passive"))
      (node (ref "S1") (pin "2") (pinfunction "2_2") (pintype "passive"))
      (node (ref "U1") (pin "2") (pinfunction "GND_2") (pintype "passive"))
      (node (ref "U3") (pin "40") (pinfunction "VSS2_40") (pintype "passive"))
      (node (ref "U3") (pin "9") (pinfunction "VSS1_9") (pintype "passive"))
      (node (ref "U4") (pin "0") (pinfunction "GND_0") (pintype "passive"))
      (node (ref "U4") (pin "1") (pinfunction "I2C_1") (pintype "passive"))
      (node (ref "U4") (pin "10") (pinfunction "TVSS_10") (pintype "passive"))
      (node (ref "U4") (pin "14") (pinfunction "TVSS_14") (pintype "passive"))
      (node (ref "U4") (pin "18") (pinfunction "AVSS_18") (pintype "passive"))
      (node (ref "U4") (pin "4") (pinfunction "DVSS_4") (pintype "passive"))
      (node (ref "U4") (pin "5") (pinfunction "PVSS_5") (pintype "passive"))
      (node (ref "U5") (pin "6") (pinfunction "GND_6") (pintype "passive"))
      (node (ref "X1") (pin "2") (pinfunction "GND_2") (pintype "passive"))
      (node (ref "X1") (pin "4") (pinfunction "GND_4") (pintype "passive"))
    )
    (net (code "32") (name "Net-(C8-Pad2)") (class "Default")
      (node (ref "C8") (pin "2") (pinfunction "2_2") (pintype "passive"))
      (node (ref "R2") (pin "1") (pinfunction "1_1") (pintype "passive"))
    )
    (net (code "33") (name "Net-(C13-Pad1)") (class "Default")
      (node (ref "C13") (pin "1") (pinfunction "1_1") (pintype "passive"))
      (node (ref "C14") (pin "2") (pinfunction "2_2") (pintype "passive"))
      (node (ref "L3") (pin "2") (pinfunction "2_2") (pintype "passive"))
    )
    (net (code "34") (name "Net-(C17-Pad1)") (class "Default")
      (node (ref "C17") (pin "1") (pinfunction "1_1") (pintype "passive"))
      (node (ref "C20") (pin "1") (pinfunction "1_1") (pintype "passive"))
      (node (ref "L4") (pin "2") (pinfunction "2_2") (pintype "passive"))
    )
    (net (code "35") (name "Net-(C21-Pad2)") (class "Default")
      (node (ref "C21") (pin "2") (pinfunction "2_2") (pintype "passive"))
      (node (ref "R28") (pin "2") (pinfunction "2_2") (pintype "passive"))
    )
    (net (code "36") (name "Net-(D1-Pad2)") (class "Default")
      (node (ref "D1") (pin "2") (pinfunction "2_2") (pintype "passive"))
      (node (ref "R14") (pin "1") (pinfunction "1_1") (pintype "passive"))
    )
    (net (code "37") (name "Net-(D1-Pad3)") (class "Default")
      (node (ref "D1") (pin "3") (pinfunction "3_3") (pintype "passive"))
      (node (ref "R13") (pin "1") (pinfunction "1_1") (pintype "passive"))
    )
    (net (code "38") (name "Net-(D1-Pad4)") (class "Default")
      (node (ref "D1") (pin "4") (pinfunction "4_4") (pintype "passive"))
      (node (ref "R11") (pin "1") (pinfunction "1_1") (pintype "passive"))
    )
    (net (code "39") (name "Net-(Q2-B)") (class "Default")
      (node (ref "Q2") (pin "1") (pinfunction "B_1") (pintype "passive"))
      (node (ref "R20") (pin "2") (pinfunction "2_2") (pintype "passive"))
      (node (ref "R22") (pin "1") (pinfunction "1_1") (pintype "passive"))
    )
    (net (code "40") (name "Net-(Q2-C)") (class "Default")
      (node (ref "J1") (pin "2") (pinfunction "2_2") (pintype "passive"))
      (node (ref "Q2") (pin "3") (pinfunction "C_3") (pintype "passive"))
    )
    (net (code "41") (name "Net-(Q2-E)") (class "Default")
      (node (ref "Q2") (pin "2") (pinfunction "E_2") (pintype "passive"))
      (node (ref "R22") (pin "2") (pinfunction "2_2") (pintype "passive"))
      (node (ref "R24") (pin "2") (pinfunction "2_2") (pintype "passive"))
    )
    (net (code "42") (name "Net-(U1-EN)") (class "Default")
      (node (ref "R1") (pin "1") (pinfunction "1_1") (pintype "passive"))
      (node (ref "U1") (pin "3") (pinfunction "EN_3") (pintype "passive"))
    )
    (net (code "43") (name "Net-(U2-BAT)") (class "Default")
      (node (ref "C9") (pin "1") (pinfunction "1_1") (pintype "passive"))
      (node (ref "R3") (pin "1") (pinfunction "1_1") (pintype "passive"))
      (node (ref "U2") (pin "6") (pinfunction "BAT_6") (pintype "passive"))
    )
    (net (code "44") (name "Net-(U2-KEY)") (class "Default")
      (node (ref "R4") (pin "1") (pinfunction "1_1") (pintype "passive"))
      (node (ref "U2") (pin "5") (pinfunction "KEY_5") (pintype "passive"))
    )
    (net (code "45") (name "Net-(U2-LE1)") (class "Default")
      (node (ref "LED1") (pin "1") (pinfunction "1_1") (pintype "passive"))
      (node (ref "U2") (pin "2") (pinfunction "LE1_2") (pintype "passive"))
    )
    (net (code "46") (name "Net-(U2-LE2)") (class "Default")
      (node (ref "R6") (pin "2") (pinfunction "2_2") (pintype "passive"))
      (node (ref "U2") (pin "3") (pinfunction "LE2_3") (pintype "passive"))
    )
    (net (code "47") (name "Net-(U2-SW)") (class "Default")
      (node (ref "L2") (pin "1") (pinfunction "1_1") (pintype "passive"))
      (node (ref "U2") (pin "7") (pinfunction "SW_7") (pintype "passive"))
    )
    (net (code "48") (name "Net-(U3-PC0)") (class "Default")
      (node (ref "R19") (pin "1") (pinfunction "1_1") (pintype "passive"))
      (node (ref "U3") (pin "37") (pinfunction "PC0_37") (pintype "passive"))
    )
    (net (code "49") (name "Net-(U3-PC1)") (class "Default")
      (node (ref "R21") (pin "1") (pinfunction "1_1") (pintype "passive"))
      (node (ref "U3") (pin "38") (pinfunction "PC1_38") (pintype "passive"))
    )
    (net (code "50") (name "Net-(U3-VLCD)") (class "Default")
      (node (ref "R15") (pin "2") (pinfunction "2_2") (pintype "passive"))
      (node (ref "U3") (pin "13") (pinfunction "VLCD_13") (pintype "passive"))
    )
    (net (code "51") (name "Net-(U4-EA)") (class "Default")
      (node (ref "R26") (pin "2") (pinfunction "2_2") (pintype "passive"))
      (node (ref "U4") (pin "32") (pinfunction "EA_32") (pintype "passive"))
    )
    (net (code "52") (name "Net-(U4-OSCIN)") (class "Default")
      (node (ref "C23") (pin "1") (pinfunction "1_1") (pintype "passive"))
      (node (ref "U4") (pin "21") (pinfunction "OSCIN_21") (pintype "passive"))
      (node (ref "X1") (pin "1") (pinfunction "OSC1_1") (pintype "passive"))
    )
    (net (code "53") (name "Net-(U4-OSTOUT)") (class "Default")
      (node (ref "C24") (pin "1") (pinfunction "1_1") (pintype "passive"))
      (node (ref "U4") (pin "22") (pinfunction "OSTOUT_22") (pintype "passive"))
      (node (ref "X1") (pin "3") (pinfunction "OSC2_3") (pintype "passive"))
    )
    (net (code "54") (name "Net-(U4-RX)") (class "Default")
      (node (ref "R27") (pin "2") (pinfunction "2_2") (pintype "passive"))
      (node (ref "R28") (pin "1") (pinfunction "1_1") (pintype "passive"))
      (node (ref "U4") (pin "17") (pinfunction "RX_17") (pintype "passive"))
    )
    (net (code "55") (name "Net-(U4-TX1)") (class "Default")
      (node (ref "L3") (pin "1") (pinfunction "1_1") (pintype "passive"))
      (node (ref "U4") (pin "11") (pinfunction "TX1_11") (pintype "passive"))
    )
    (net (code "56") (name "Net-(U4-TX2)") (class "Default")
      (node (ref "L4") (pin "1") (pinfunction "1_1") (pintype "passive"))
      (node (ref "U4") (pin "13") (pinfunction "TX2_13") (pintype "passive"))
    )
    (net (code "57") (name "Net-(U4-VMID)") (class "Default")
      (node (ref "C22") (pin "2") (pinfunction "2_2") (pintype "passive"))
      (node (ref "R27") (pin "1") (pinfunction "1_1") (pintype "passive"))
      (node (ref "U4") (pin "16") (pinfunction "VMID_16") (pintype "passive"))
    )
    (net (code "58") (name "Net-(U5-IN1)") (class "Default")
      (node (ref "R29") (pin "2") (pinfunction "2_2") (pintype "passive"))
      (node (ref "U5") (pin "2") (pinfunction "IN1_2") (pintype "passive"))
    )
    (net (code "59") (name "Net-(U5-IN2)") (class "Default")
      (node (ref "R30") (pin "2") (pinfunction "2_2") (pintype "passive"))
      (node (ref "U5") (pin "3") (pinfunction "IN2_3") (pintype "passive"))
    )
    (net (code "60") (name "Net-(U5-IN3)") (class "Default")
      (node (ref "R31") (pin "2") (pinfunction "2_2") (pintype "passive"))
      (node (ref "U5") (pin "4") (pinfunction "IN3_4") (pintype "passive"))
    )
    (net (code "61") (name "Net-(U5-IN4)") (class "Default")
      (node (ref "R32") (pin "2") (pinfunction "2_2") (pintype "passive"))
      (node (ref "U5") (pin "5") (pinfunction "IN4_5") (pintype "passive"))
    )
    (net (code "62") (name "VDD") (class "Default")
      (node (ref "C4") (pin "2") (pinfunction "2_2") (pintype "passive"))
      (node (ref "L1") (pin "2") (pinfunction "2_2") (pintype "passive"))
      (node (ref "Q1") (pin "2") (pinfunction "S_2") (pintype "passive"))
      (node (ref "U1") (pin "5") (pinfunction "VOUT_5") (pintype "passive"))
    )
    (net (code "63") (name "V_IN") (class "Default")
      (node (ref "C6") (pin "1") (pinfunction "1_1") (pintype "passive"))
      (node (ref "P1") (pin "2") (pinfunction "2_2") (pintype "passive"))
      (node (ref "R2") (pin "2") (pinfunction "2_2") (pintype "passive"))
      (node (ref "U2") (pin "1") (pinfunction "VIN_1") (pintype "passive"))
      (node (ref "USB1") (pin "A9") (pinfunction "VBUS_A9") (pintype "passive"))
      (node (ref "USB1") (pin "B9") (pinfunction "VBUS_B9") (pintype "passive"))
    )
    (net (code "64") (name "unconnected-(J1-Pad3)") (class "Default")
      (node (ref "J1") (pin "3") (pinfunction "3_3") (pintype "passive"))
    )
    (net (code "65") (name "unconnected-(J1-Pad4)") (class "Default")
      (node (ref "J1") (pin "4") (pinfunction "4_4") (pintype "passive"))
    )
    (net (code "66") (name "unconnected-(U1-NC-Pad4)") (class "Default")
      (node (ref "U1") (pin "4") (pinfunction "NC_4") (pintype "passive"))
    )
    (net (code "67") (name "unconnected-(U2-LE3-Pad4)") (class "Default")
      (node (ref "U2") (pin "4") (pinfunction "LE3_4") (pintype "passive"))
    )
    (net (code "68") (name "unconnected-(U3-PA3-Pad4)") (class "Default")
      (node (ref "U3") (pin "4") (pinfunction "PA3_4") (pintype "passive+no_connect"))
    )
    (net (code "69") (name "unconnected-(U3-PA4-Pad5)") (class "Default")
      (node (ref "U3") (pin "5") (pinfunction "PA4_5") (pintype "passive+no_connect"))
    )
    (net (code "70") (name "unconnected-(U3-PA5-Pad6)") (class "Default")
      (node (ref "U3") (pin "6") (pinfunction "PA5_6") (pintype "passive+no_connect"))
    )
    (net (code "71") (name "unconnected-(U3-PA6-Pad7)") (class "Default")
      (node (ref "U3") (pin "7") (pinfunction "PA6_7") (pintype "passive+no_connect"))
    )
    (net (code "72") (name "unconnected-(U3-PA7-Pad8)") (class "Default")
      (node (ref "U3") (pin "8") (pinfunction "PA7_8") (pintype "passive+no_connect"))
    )
    (net (code "73") (name "unconnected-(U3-PB3-Pad27)") (class "Default")
      (node (ref "U3") (pin "27") (pinfunction "PB3_27") (pintype "passive+no_connect"))
    )
    (net (code "74") (name "unconnected-(U3-PB6-Pad30)") (class "Default")
      (node (ref "U3") (pin "30") (pinfunction "PB6_30") (pintype "passive+no_connect"))
    )
    (net (code "75") (name "unconnected-(U3-PB7-Pad31)") (class "Default")
      (node (ref "U3") (pin "31") (pinfunction "PB7_31") (pintype "passive+no_connect"))
    )
    (net (code "76") (name "unconnected-(U3-PD1-Pad21)") (class "Default")
      (node (ref "U3") (pin "21") (pinfunction "PD1_21") (pintype "passive+no_connect"))
    )
    (net (code "77") (name "unconnected-(U3-PD3-Pad23)") (class "Default")
      (node (ref "U3") (pin "23") (pinfunction "PD3_23") (pintype "passive+no_connect"))
    )
    (net (code "78") (name "unconnected-(U3-PD4-Pad33)") (class "Default")
      (node (ref "U3") (pin "33") (pinfunction "PD4_33") (pintype "passive+no_connect"))
    )
    (net (code "79") (name "unconnected-(U3-PD5-Pad34)") (class "Default")
      (node (ref "U3") (pin "34") (pinfunction "PD5_34") (pintype "passive+no_connect"))
    )
    (net (code "80") (name "unconnected-(U3-PD6-Pad35)") (class "Default")
      (node (ref "U3") (pin "35") (pinfunction "PD6_35") (pintype "passive+no_connect"))
    )
    (net (code "81") (name "unconnected-(U3-PE0-Pad14)") (class "Default")
      (node (ref "U3") (pin "14") (pinfunction "PE0_14") (pintype "passive+no_connect"))
    )
    (net (code "82") (name "unconnected-(U3-PE1-Pad15)") (class "Default")
      (node (ref "U3") (pin "15") (pinfunction "PE1_15") (pintype "passive+no_connect"))
    )
    (net (code "83") (name "unconnected-(U3-PE2-Pad16)") (class "Default")
      (node (ref "U3") (pin "16") (pinfunction "PE2_16") (pintype "passive+no_connect"))
    )
    (net (code "84") (name "unconnected-(U3-PE3-Pad17)") (class "Default")
      (node (ref "U3") (pin "17") (pinfunction "PE3_17") (pintype "passive+no_connect"))
    )
    (net (code "85") (name "unconnected-(U3-PE4-Pad18)") (class "Default")
      (node (ref "U3") (pin "18") (pinfunction "PE4_18") (pintype "passive+no_connect"))
    )
    (net (code "86") (name "unconnected-(U3-PE5-Pad19)") (class "Default")
      (node (ref "U3") (pin "19") (pinfunction "PE5_19") (pintype "passive+no_connect"))
    )
    (net (code "87") (name "unconnected-(U3-PF0-Pad32)") (class "Default")
      (node (ref "U3") (pin "32") (pinfunction "PF0_32") (pintype "passive+no_connect"))
    )
    (net (code "88") (name "unconnected-(U4-AUX1-Pad19)") (class "Default")
      (node (ref "U4") (pin "19") (pinfunction "AUX1_19") (pintype "passive+no_connect"))
    )
    (net (code "89") (name "unconnected-(U4-AUX2-Pad20)") (class "Default")
      (node (ref "U4") (pin "20") (pinfunction "AUX2_20") (pintype "passive+no_connect"))
    )
    (net (code "90") (name "unconnected-(U4-D1-Pad25)") (class "Default")
      (node (ref "U4") (pin "25") (pinfunction "D1_25") (pintype "passive+no_connect"))
    )
    (net (code "91") (name "unconnected-(U4-D2-Pad26)") (class "Default")
      (node (ref "U4") (pin "26") (pinfunction "D2_26") (pintype "passive+no_connect"))
    )
    (net (code "92") (name "unconnected-(U4-D3-Pad27)") (class "Default")
      (node (ref "U4") (pin "27") (pinfunction "D3_27") (pintype "passive+no_connect"))
    )
    (net (code "93") (name "unconnected-(U4-D4-Pad28)") (class "Default")
      (node (ref "U4") (pin "28") (pinfunction "D4_28") (pintype "passive+no_connect"))
    )
    (net (code "94") (name "unconnected-(U4-IRQ-Pad23)") (class "Default")
      (node (ref "U4") (pin "23") (pinfunction "IRQ_23") (pintype "passive+no_connect"))
    )
    (net (code "95") (name "unconnected-(U4-SIGIN-Pad7)") (class "Default")
      (node (ref "U4") (pin "7") (pinfunction "SIGIN_7") (pintype "passive+no_connect"))
    )
    (net (code "96") (name "unconnected-(U4-SIGOUT-Pad8)") (class "Default")
      (node (ref "U4") (pin "8") (pinfunction "SIGOUT_8") (pintype "passive+no_connect"))
    )
    (net (code "97") (name "unconnected-(U4-TEST-Pad9)") (class "Default")
      (node (ref "U4") (pin "9") (pinfunction "TEST_9") (pintype "passive+no_connect"))
    )
    (net (code "98") (name "unconnected-(USB1-CC1-PadA5)") (class "Default")
      (node (ref "USB1") (pin "A5") (pinfunction "CC1_A5") (pintype "passive+no_connect"))
    )
    (net (code "99") (name "unconnected-(USB1-CC2-PadB5)") (class "Default")
      (node (ref "USB1") (pin "B5") (pinfunction "CC2_B5") (pintype "passive+no_connect"))
    )
  )
)
